# SPI-UART.net
KiCad netlist of a schematic drawn in Altium Designer
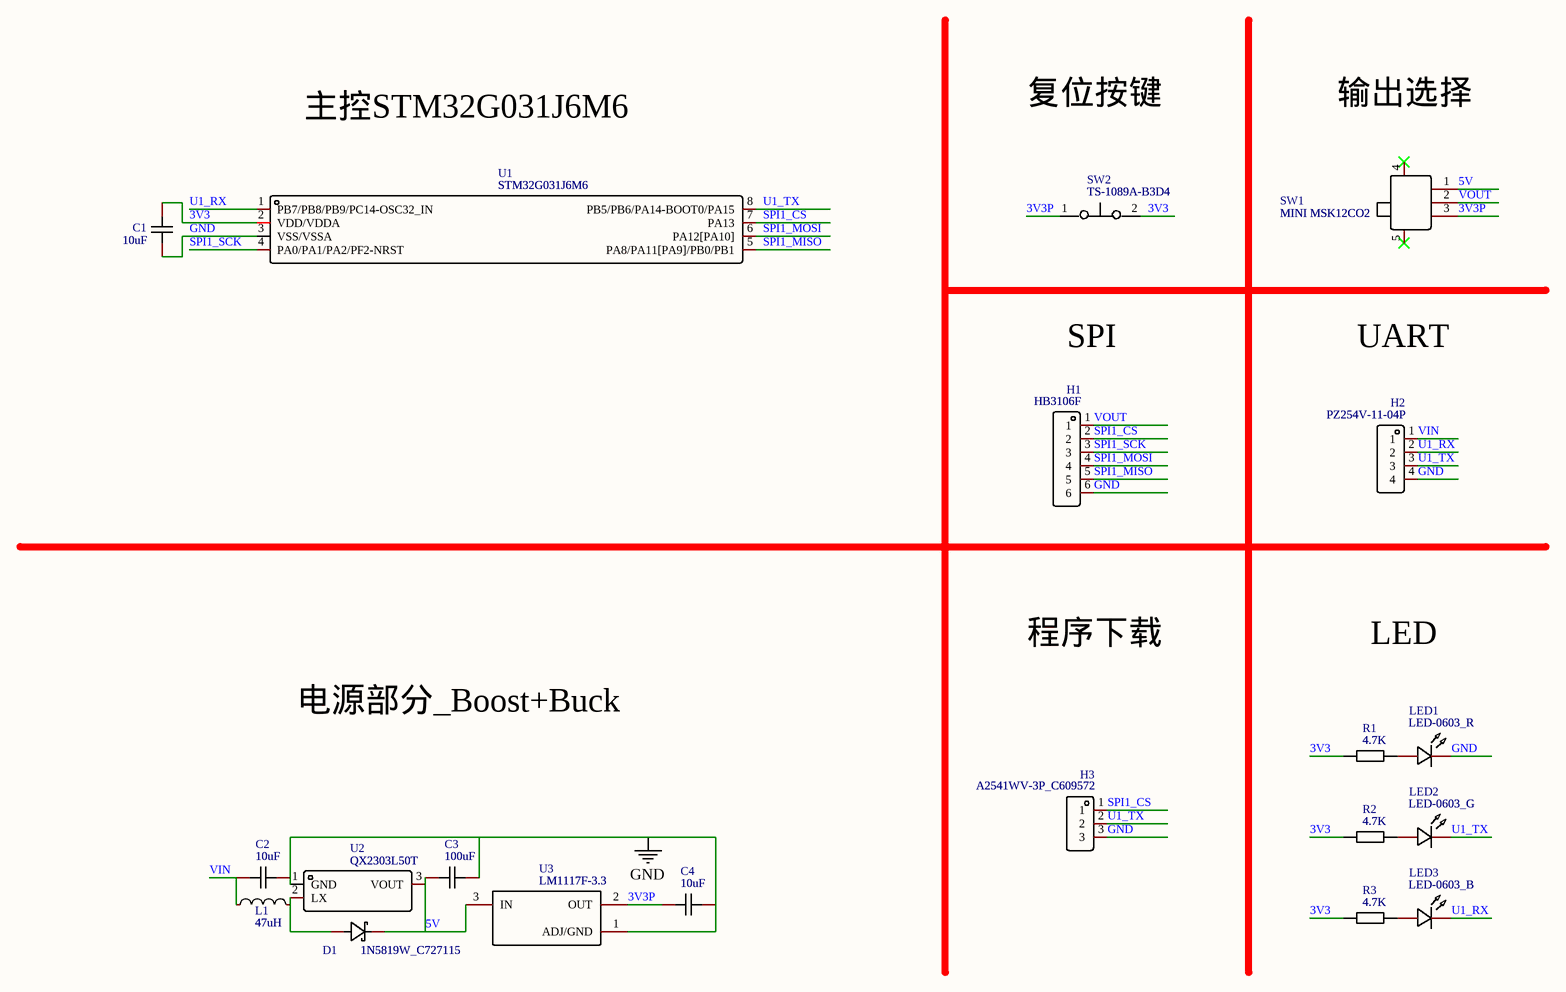
[diagram p0: SPI-UART.schdoc]

(export (version "E")
  (design (tool "Eeschema 10.0.6"))
  (components
    (comp (ref "C1")
      (value "10uF")
      (fields
        (field (name "NAME") "10uF")
        (field (name "MANUFACTURER") "MuRata")
        (field (name "MANUFACTURER PART") "GRM155R61A106ME44D")
      )
      (libsource (lib "altium-import") (part "root_3_10uF_"))
    )
    (comp (ref "C2")
      (value "10uF")
      (fields
        (field (name "NAME") "10uF")
        (field (name "MANUFACTURER") "MuRata")
        (field (name "MANUFACTURER PART") "GRM155R61A106ME44D")
      )
      (libsource (lib "altium-import") (part "root_0_10uF_"))
    )
    (comp (ref "C3")
      (value "100uF")
      (fields
        (field (name "NAME") "100uF")
        (field (name "MANUFACTURER") "Murata Electronics")
        (field (name "MANUFACTURER PART") "GRM31CR61A107ME05L")
      )
      (libsource (lib "altium-import") (part "root_0_100uF_"))
    )
    (comp (ref "C4")
      (value "10uF")
      (fields
        (field (name "NAME") "10uF")
        (field (name "MANUFACTURER") "MuRata")
        (field (name "MANUFACTURER PART") "GRM155R61A106ME44D")
      )
      (libsource (lib "altium-import") (part "root_0_10uF_"))
    )
    (comp (ref "D1")
      (value "1N5819W_C727115")
      (fields
        (field (name "NAME") "1N5819W_C727115")
        (field (name "MANUFACTURER") "TWGMC")
        (field (name "MANUFACTURER PART") "1N5819W")
      )
      (libsource (lib "altium-import") (part "root_0_1N5819W_C727115_"))
    )
    (comp (ref "H1")
      (value "HB3106F")
      (fields (field (name "NAME") "HB3106F") (field (name "MANUFACTURER") "FOXCONN(富士康)"))
      (libsource (lib "altium-import") (part "root_0_HB3106F_"))
    )
    (comp (ref "H2")
      (value "PZ254V-11-04P")
      (fields (field (name "NAME") "PZ254V-11-04P") (field (name "MANUFACTURER") "XFCN"))
      (libsource (lib "altium-import") (part "root_0_PZ254V-11-04P_"))
    )
    (comp (ref "H3")
      (value "A2541WV-3P_C609572")
      (fields
        (field (name "NAME") "A2541WV-3P_C609572")
        (field (name "MANUFACTURER") "CJT(Changjiang Connectors)")
        (field (name "MANUFACTURER PART") "A2541WV-3P")
      )
      (libsource (lib "altium-import") (part "root_0_A2541WV-3P_C609572_"))
    )
    (comp (ref "L1")
      (value "47uH")
      (fields
        (field (name "NAME") "47uH")
        (field (name "MANUFACTURER") "Taiyo Yuden")
        (field (name "MANUFACTURER PART") "NRS6012T470MMGJ")
      )
      (libsource (lib "altium-import") (part "root_0_47uH_"))
    )
    (comp (ref "LED1")
      (value "LED-0603_R")
      (fields
        (field (name "NAME") "LED-0603_R")
        (field (name "MANUFACTURER") "EVERLIGHT(台湾亿光)")
        (field (name "MANUFACTURER PART") "19-217/R6C-AL1M2VY/3T")
      )
      (libsource (lib "altium-import") (part "root_0_LED-0603_R_"))
    )
    (comp (ref "LED2")
      (value "LED-0603_G")
      (fields
        (field (name "NAME") "LED-0603_G")
        (field (name "MANUFACTURER") "EVERLIGHT(台湾亿光)")
        (field (name "MANUFACTURER PART") "19-217/GHC-YR1S2/3T")
      )
      (libsource (lib "altium-import") (part "root_0_LED-0603_G_"))
    )
    (comp (ref "LED3")
      (value "LED-0603_B")
      (fields
        (field (name "NAME") "LED-0603_B")
        (field (name "MANUFACTURER") "EVERLIGHT(台湾亿光)")
        (field (name "MANUFACTURER PART") "19-217/BHC-ZL1M2RY/3T")
      )
      (libsource (lib "altium-import") (part "root_0_LED-0603_B_"))
    )
    (comp (ref "R1")
      (value "4.7K")
      (fields
        (field (name "NAME") "4.7K")
        (field (name "MANUFACTURER") "UniOhm")
        (field (name "MANUFACTURER PART") "0402WGJ0472TCE")
      )
      (libsource (lib "altium-import") (part "root_0_4.7K_"))
    )
    (comp (ref "R2")
      (value "4.7K")
      (fields
        (field (name "NAME") "4.7K")
        (field (name "MANUFACTURER") "UniOhm")
        (field (name "MANUFACTURER PART") "0402WGJ0472TCE")
      )
      (libsource (lib "altium-import") (part "root_0_4.7K_"))
    )
    (comp (ref "R3")
      (value "4.7K")
      (fields
        (field (name "NAME") "4.7K")
        (field (name "MANUFACTURER") "UniOhm")
        (field (name "MANUFACTURER PART") "0402WGJ0472TCE")
      )
      (libsource (lib "altium-import") (part "root_0_4.7K_"))
    )
    (comp (ref "SW1")
      (value "MINI MSK12CO2")
      (fields (field (name "NAME") "MINI MSK12CO2") (field (name "MANUFACTURER") "SHOU HAN(首韩)"))
      (libsource (lib "altium-import") (part "root_3_MINI MSK12CO2_"))
    )
    (comp (ref "SW2")
      (value "TS-1089A-B3D4")
      (description "贴片1N4148")
      (fields (field (name "NAME") "TS-1089A-B3D4") (field (name "MANUFACTURER") "Yuandi"))
      (libsource (lib "altium-import") (part "root_0_TS-1089A-B3D4_"))
    )
    (comp (ref "U1")
      (value "STM32G031J6M6")
      (fields (field (name "NAME") "STM32G031J6M6") (field (name "MANUFACTURER") "STMicroelectronics"))
      (libsource (lib "altium-import") (part "root_0_STM32G031J6M6_"))
    )
    (comp (ref "U2")
      (value "QX2303L50T")
      (fields (field (name "NAME") "QX2303L50T") (field (name "MANUFACTURER") "QX Micro Devices"))
      (libsource (lib "altium-import") (part "root_0_QX2303L50T_"))
    )
    (comp (ref "U3")
      (value "LM1117F-3.3")
      (fields (field (name "NAME") "LM1117F-3.3") (field (name "MANUFACTURER") "HTC"))
      (libsource (lib "altium-import") (part "root_0_LM1117F-3.3_"))
    )
  )
  (nets
    (net (code "1") (name "/3V3") (class "Default")
      (node (ref "C1") (pin "1") (pinfunction "1_1") (pintype "passive"))
      (node (ref "R1") (pin "1") (pinfunction "1_1") (pintype "passive"))
      (node (ref "R2") (pin "1") (pinfunction "1_1") (pintype "passive"))
      (node (ref "R3") (pin "1") (pinfunction "1_1") (pintype "passive"))
      (node (ref "SW2") (pin "2") (pinfunction "2_2") (pintype "passive"))
      (node (ref "U1") (pin "2") (pinfunction "VDD/VDDA_2") (pintype "passive"))
    )
    (net (code "2") (name "/3V3P") (class "Default")
      (node (ref "C4") (pin "1") (pinfunction "1_1") (pintype "passive"))
      (node (ref "SW1") (pin "3") (pinfunction "3_3") (pintype "passive"))
      (node (ref "SW2") (pin "1") (pinfunction "1_1") (pintype "passive"))
      (node (ref "U3") (pin "2") (pinfunction "OUT_2") (pintype "passive"))
    )
    (net (code "3") (name "/5V") (class "Default")
      (node (ref "C3") (pin "2") (pinfunction "2_2") (pintype "passive"))
      (node (ref "D1") (pin "1") (pinfunction "C_1") (pintype "passive"))
      (node (ref "SW1") (pin "1") (pinfunction "1_1") (pintype "passive"))
      (node (ref "U2") (pin "3") (pinfunction "VOUT_3") (pintype "passive"))
      (node (ref "U3") (pin "3") (pinfunction "IN_3") (pintype "passive"))
    )
    (net (code "4") (name "/SPI1_CS") (class "Default")
      (node (ref "H1") (pin "2") (pinfunction "2_2") (pintype "passive"))
      (node (ref "H3") (pin "1") (pinfunction "1_1") (pintype "passive"))
      (node (ref "U1") (pin "7") (pinfunction "PA13_7") (pintype "passive"))
    )
    (net (code "5") (name "/SPI1_MISO") (class "Default")
      (node (ref "H1") (pin "5") (pinfunction "5_5") (pintype "passive"))
      (node (ref "U1") (pin "5") (pinfunction "PA8/PA11[PA9]/PB0/PB1_5") (pintype "passive"))
    )
    (net (code "6") (name "/SPI1_MOSI") (class "Default")
      (node (ref "H1") (pin "4") (pinfunction "4_4") (pintype "passive"))
      (node (ref "U1") (pin "6") (pinfunction "PA12[PA10]_6") (pintype "passive"))
    )
    (net (code "7") (name "/SPI1_SCK") (class "Default")
      (node (ref "H1") (pin "3") (pinfunction "3_3") (pintype "passive"))
      (node (ref "U1") (pin "4") (pinfunction "PA0/PA1/PA2/PF2-NRST_4") (pintype "passive"))
    )
    (net (code "8") (name "/U1_RX") (class "Default")
      (node (ref "H2") (pin "2") (pinfunction "2_2") (pintype "passive"))
      (node (ref "LED3") (pin "2") (pinfunction "2_2") (pintype "passive"))
      (node (ref "U1") (pin "1") (pinfunction "PB7/PB8/PB9/PC14-OSC32_IN_1") (pintype "passive"))
    )
    (net (code "9") (name "/U1_TX") (class "Default")
      (node (ref "H2") (pin "3") (pinfunction "3_3") (pintype "passive"))
      (node (ref "H3") (pin "2") (pinfunction "2_2") (pintype "passive"))
      (node (ref "LED2") (pin "2") (pinfunction "2_2") (pintype "passive"))
      (node (ref "U1") (pin "8") (pinfunction "PB5/PB6/PA14-BOOT0/PA15_8") (pintype "passive"))
    )
    (net (code "10") (name "/VIN") (class "Default")
      (node (ref "C2") (pin "1") (pinfunction "1_1") (pintype "passive"))
      (node (ref "H2") (pin "1") (pinfunction "1_1") (pintype "passive"))
      (node (ref "L1") (pin "1") (pinfunction "1_1") (pintype "passive"))
    )
    (net (code "11") (name "/VOUT") (class "Default")
      (node (ref "H1") (pin "1") (pinfunction "1_1") (pintype "passive"))
      (node (ref "SW1") (pin "2") (pinfunction "2_2") (pintype "passive"))
    )
    (net (code "12") (name "GND") (class "Default")
      (node (ref "C1") (pin "2") (pinfunction "2_2") (pintype "passive"))
      (node (ref "C2") (pin "2") (pinfunction "2_2") (pintype "passive"))
      (node (ref "C3") (pin "1") (pinfunction "1_1") (pintype "passive"))
      (node (ref "C4") (pin "2") (pinfunction "2_2") (pintype "passive"))
      (node (ref "H1") (pin "6") (pinfunction "6_6") (pintype "passive"))
      (node (ref "H2") (pin "4") (pinfunction "4_4") (pintype "passive"))
      (node (ref "H3") (pin "3") (pinfunction "3_3") (pintype "passive"))
      (node (ref "LED1") (pin "2") (pinfunction "2_2") (pintype "passive"))
      (node (ref "U1") (pin "3") (pinfunction "VSS/VSSA_3") (pintype "passive"))
      (node (ref "U2") (pin "1") (pinfunction "GND_1") (pintype "passive"))
      (node (ref "U3") (pin "1") (pinfunction "ADJ/GND_1") (pintype "passive"))
    )
    (net (code "13") (name "Net-(D1-A)") (class "Default")
      (node (ref "D1") (pin "2") (pinfunction "A_2") (pintype "passive"))
      (node (ref "L1") (pin "2") (pinfunction "2_2") (pintype "passive"))
      (node (ref "U2") (pin "2") (pinfunction "LX_2") (pintype "passive"))
    )
    (net (code "14") (name "Net-(LED1-Pad1)") (class "Default")
      (node (ref "LED1") (pin "1") (pinfunction "1_1") (pintype "passive"))
      (node (ref "R1") (pin "2") (pinfunction "2_2") (pintype "passive"))
    )
    (net (code "15") (name "Net-(LED2-Pad1)") (class "Default")
      (node (ref "LED2") (pin "1") (pinfunction "1_1") (pintype "passive"))
      (node (ref "R2") (pin "2") (pinfunction "2_2") (pintype "passive"))
    )
    (net (code "16") (name "Net-(LED3-Pad1)") (class "Default")
      (node (ref "LED3") (pin "1") (pinfunction "1_1") (pintype "passive"))
      (node (ref "R3") (pin "2") (pinfunction "2_2") (pintype "passive"))
    )
    (net (code "17") (name "unconnected-(SW1-Pad4)") (class "Default")
      (node (ref "SW1") (pin "4") (pinfunction "4_4") (pintype "passive+no_connect"))
    )
    (net (code "18") (name "unconnected-(SW1-Pad5)") (class "Default")
      (node (ref "SW1") (pin "5") (pinfunction "5_5") (pintype "passive+no_connect"))
    )
  )
)
